# cm_filter_ch0_a.net
KiCad netlist of a schematic drawn in Altium Designer
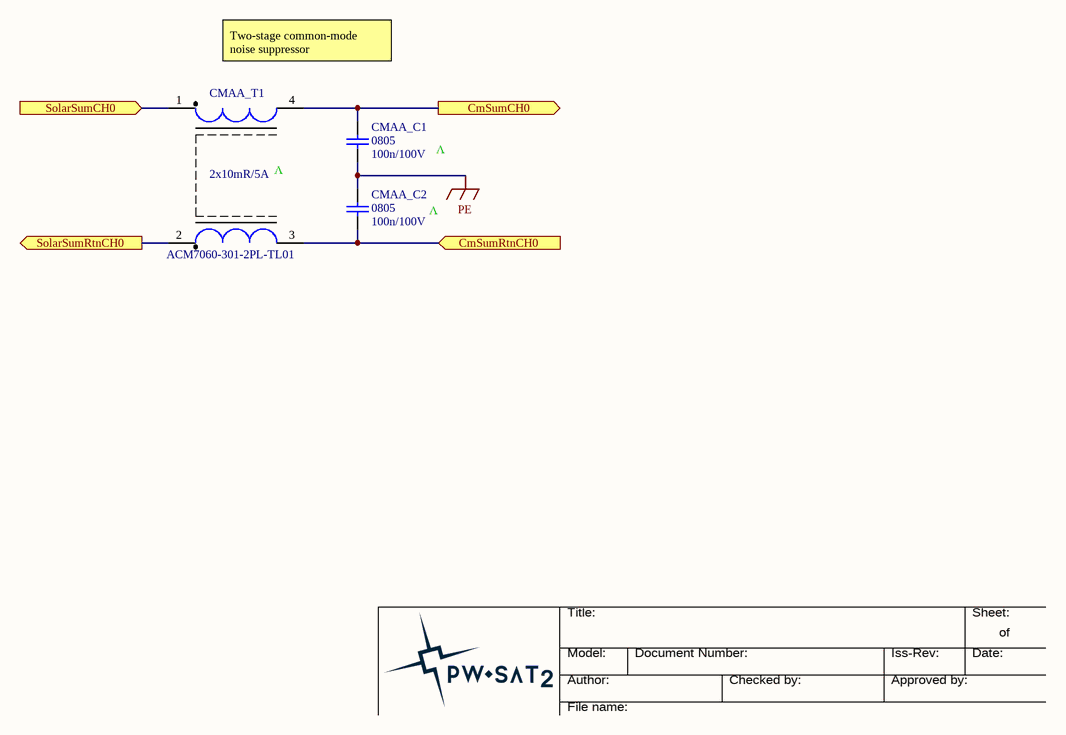
[diagram p0: cm_filter_ch0_a.SchDoc]

(export (version "E")
  (design (tool "Eeschema 10.0.6"))
  (components
    (comp (ref "CMAA_C1")
      (value "100n/100V")
      (footprint "SMD_Capacitor_0805")
      (description "Ceramic Cap Kemet COTS 100n/100V X7R 0805")
      (fields
        (field (name "MANUFACTURERPARTNUMBER") "C0805T104K1RCLTU")
        (field (name "MANUFACTURER") "Kemet")
        (field (name "PACKAGE") "0805")
      )
      (libsource (lib "capacitors") (part "Cer_C0805T104K1RCLTU"))
    )
    (comp (ref "CMAA_C2")
      (value "100n/100V")
      (footprint "SMD_Capacitor_0805")
      (description "Ceramic Cap Kemet COTS 100n/100V X7R 0805")
      (fields
        (field (name "MANUFACTURERPARTNUMBER") "C0805T104K1RCLTU")
        (field (name "MANUFACTURER") "Kemet")
        (field (name "PACKAGE") "0805")
      )
      (libsource (lib "capacitors") (part "Cer_C0805T104K1RCLTU"))
    )
    (comp (ref "CMAA_T1")
      (value "2x10mR/5A")
      (footprint "TDK_ACM7060")
      (description "TDK ACM7060-301 Common Mode Choke")
      (fields
        (field (name "MANUFACTURER") "TDK")
        (field (name "MANUFACTURERPARTNUMBER") "ACM7060-301-2PL-TL01")
      )
      (libsource (lib "inductors") (part "ACM7060-301-2PL-TL01"))
    )
  )
  (nets
    (net (code "1") (name "/CmSumCH0") (class "Default")
      (node (ref "CMAA_C1") (pin "1") (pinfunction "1_1") (pintype "passive"))
      (node (ref "CMAA_T1") (pin "4") (pinfunction "4_4") (pintype "passive"))
    )
    (net (code "2") (name "/CmSumRtnCH0") (class "Default")
      (node (ref "CMAA_C2") (pin "2") (pinfunction "2_2") (pintype "passive"))
      (node (ref "CMAA_T1") (pin "3") (pinfunction "3_3") (pintype "passive"))
    )
    (net (code "3") (name "/SolarSumCH0") (class "Default")
      (node (ref "CMAA_T1") (pin "1") (pinfunction "1_1") (pintype "passive"))
    )
    (net (code "4") (name "/SolarSumRtnCH0") (class "Default")
      (node (ref "CMAA_T1") (pin "2") (pinfunction "2_2") (pintype "passive"))
    )
    (net (code "5") (name "PE") (class "Default")
      (node (ref "CMAA_C1") (pin "2") (pinfunction "2_2") (pintype "passive"))
      (node (ref "CMAA_C2") (pin "1") (pinfunction "1_1") (pintype "passive"))
    )
  )
)
